# TAStm32_v4.net
KiCad netlist of a schematic drawn in EAGLE
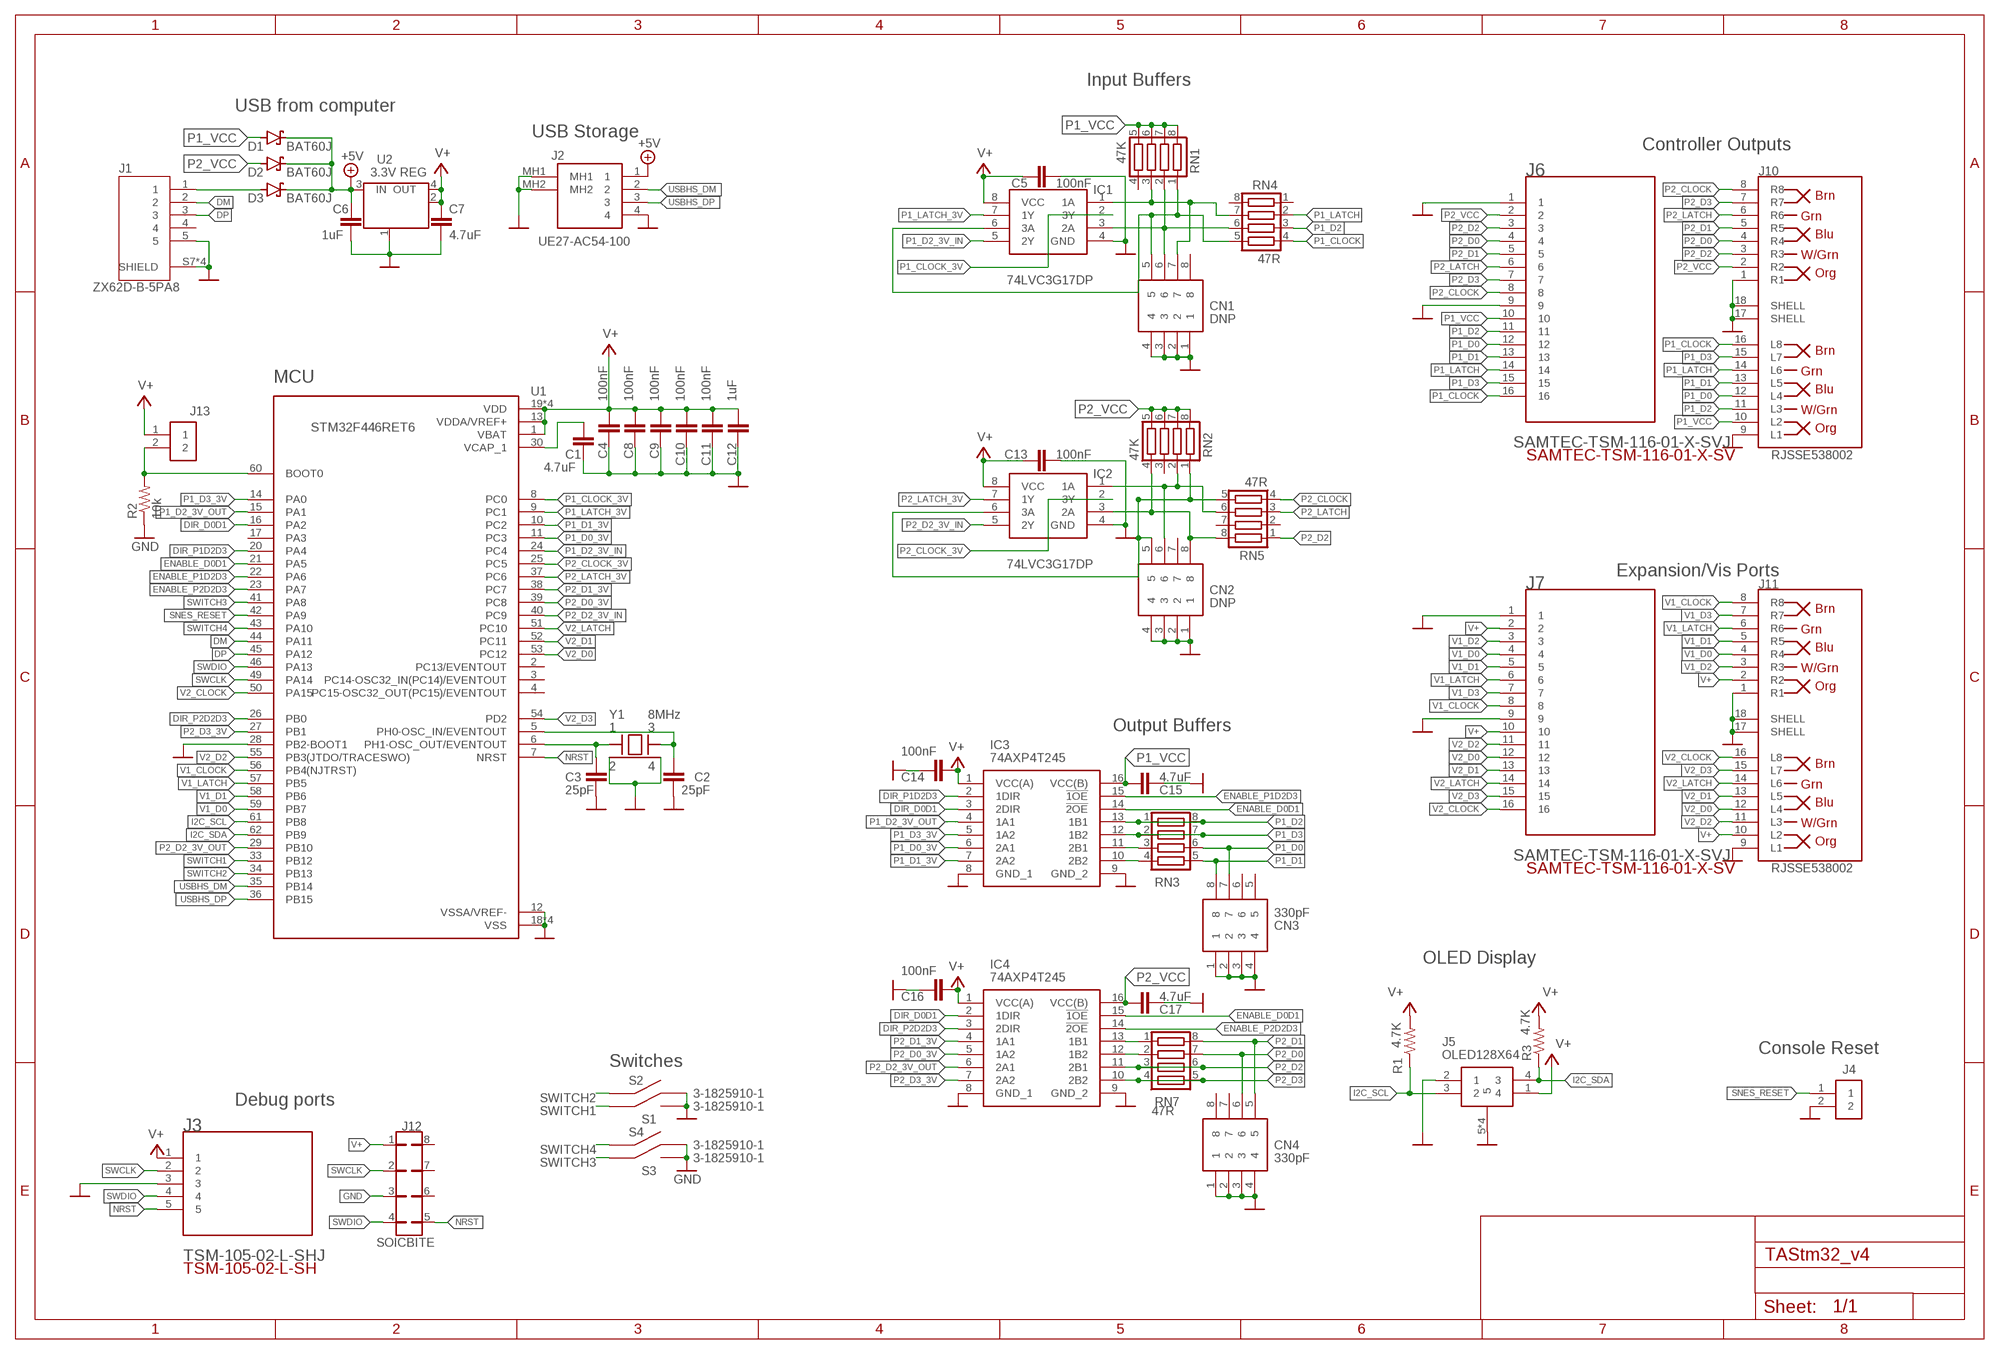
[diagram p0: schematic, sheet 1]

(export (version "E")
  (design (tool "Eeschema 10.0.6"))
  (components
    (comp (ref "C1")
      (value "4.7uF")
      (footprint "eagle-import:C0603K")
      (libsource (lib "eagle-import") (part "C-EUC0603K"))
    )
    (comp (ref "C2")
      (value "25pF")
      (footprint "eagle-import:C0603K")
      (libsource (lib "eagle-import") (part "C-EUC0603K"))
    )
    (comp (ref "C3")
      (value "25pF")
      (footprint "eagle-import:C0603K")
      (libsource (lib "eagle-import") (part "C-EUC0603K"))
    )
    (comp (ref "C4")
      (value "100nF")
      (footprint "eagle-import:C0603K")
      (libsource (lib "eagle-import") (part "C-EUC0603K"))
    )
    (comp (ref "C5")
      (value "100nF")
      (footprint "eagle-import:C0603K")
      (libsource (lib "eagle-import") (part "C-EUC0603K"))
    )
    (comp (ref "C6")
      (value "1uF")
      (footprint "eagle-import:C0603K")
      (libsource (lib "eagle-import") (part "C-EUC0603K"))
    )
    (comp (ref "C7")
      (value "4.7uF")
      (footprint "eagle-import:C0603K")
      (libsource (lib "eagle-import") (part "C-EUC0603K"))
    )
    (comp (ref "C8")
      (value "100nF")
      (footprint "eagle-import:C0603K")
      (libsource (lib "eagle-import") (part "C-EUC0603K"))
    )
    (comp (ref "C9")
      (value "100nF")
      (footprint "eagle-import:C0603K")
      (libsource (lib "eagle-import") (part "C-EUC0603K"))
    )
    (comp (ref "C10")
      (value "100nF")
      (footprint "eagle-import:C0603K")
      (libsource (lib "eagle-import") (part "C-EUC0603K"))
    )
    (comp (ref "C11")
      (value "100nF")
      (footprint "eagle-import:C0603K")
      (libsource (lib "eagle-import") (part "C-EUC0603K"))
    )
    (comp (ref "C12")
      (value "1uF")
      (footprint "eagle-import:C0603K")
      (libsource (lib "eagle-import") (part "C-EUC0603K"))
    )
    (comp (ref "C13")
      (value "100nF")
      (footprint "eagle-import:C0603K")
      (libsource (lib "eagle-import") (part "C-EUC0603K"))
    )
    (comp (ref "C14")
      (value "100nF")
      (footprint "eagle-import:C0603K")
      (libsource (lib "eagle-import") (part "C-EUC0603K"))
    )
    (comp (ref "C15")
      (value "4.7uF")
      (footprint "eagle-import:C0603K")
      (libsource (lib "eagle-import") (part "C-EUC0603K"))
    )
    (comp (ref "C16")
      (value "100nF")
      (footprint "eagle-import:C0603K")
      (libsource (lib "eagle-import") (part "C-EUC0603K"))
    )
    (comp (ref "C17")
      (value "4.7uF")
      (footprint "eagle-import:C0603K")
      (libsource (lib "eagle-import") (part "C-EUC0603K"))
    )
    (comp (ref "CN1")
      (value "DNP")
      (footprint "eagle-import:CA0612KRX7R7BB104")
      (fields
        (field (name "MANUFACTURER_PART_NUMBER") "CA0612KRX7R7BB104")
        (field (name "MOUSER_PART_NUMBER") "603-CA612KRX7R7BB104")
      )
      (libsource (lib "eagle-import") (part "CA0612KRX7R7BB104"))
    )
    (comp (ref "CN2")
      (value "DNP")
      (footprint "eagle-import:CA0612KRX7R7BB104")
      (fields
        (field (name "MANUFACTURER_PART_NUMBER") "CA0612KRX7R7BB104")
        (field (name "MOUSER_PART_NUMBER") "603-CA612KRX7R7BB104")
      )
      (libsource (lib "eagle-import") (part "CA0612KRX7R7BB104"))
    )
    (comp (ref "CN3")
      (value "330pF")
      (footprint "eagle-import:CA0612KRX7R7BB104")
      (fields
        (field (name "MANUFACTURER_PART_NUMBER") "CA0612KRX7R7BB104")
        (field (name "MOUSER_PART_NUMBER") "603-CA612KRX7R7BB104")
      )
      (libsource (lib "eagle-import") (part "CA0612KRX7R7BB104"))
    )
    (comp (ref "CN4")
      (value "330pF")
      (footprint "eagle-import:CA0612KRX7R7BB104")
      (fields
        (field (name "MANUFACTURER_PART_NUMBER") "CA0612KRX7R7BB104")
        (field (name "MOUSER_PART_NUMBER") "603-CA612KRX7R7BB104")
      )
      (libsource (lib "eagle-import") (part "CA0612KRX7R7BB104"))
    )
    (comp (ref "D1")
      (value "BAT60J")
      (footprint "eagle-import:DIODE_SOD323_ST")
      (libsource (lib "eagle-import") (part "DIODE_BAT60J"))
    )
    (comp (ref "D2")
      (value "BAT60J")
      (footprint "eagle-import:DIODE_SOD323_ST")
      (libsource (lib "eagle-import") (part "DIODE_BAT60J"))
    )
    (comp (ref "D3")
      (value "BAT60J")
      (footprint "eagle-import:DIODE_SOD323_ST")
      (libsource (lib "eagle-import") (part "DIODE_BAT60J"))
    )
    (comp (ref "IC1")
      (value "74LVC3G17DP")
      (footprint "eagle-import:SOP65P400X110-8N")
      (fields
        (field (name "MANUFACTURER_PART_NUMBER") "74HCT3G07DP-Q100H")
        (field (name "RS_PART_NUMBER") "1532947P")
      )
      (libsource (lib "eagle-import") (part "74HCT3G07DP-Q100H"))
    )
    (comp (ref "IC2")
      (value "74LVC3G17DP")
      (footprint "eagle-import:SOP65P400X110-8N")
      (fields
        (field (name "MANUFACTURER_PART_NUMBER") "74HCT3G07DP-Q100H")
        (field (name "RS_PART_NUMBER") "1532947P")
      )
      (libsource (lib "eagle-import") (part "74HCT3G07DP-Q100H"))
    )
    (comp (ref "IC3")
      (value "74AXP4T245")
      (footprint "eagle-import:SOP65P640X110-16N")
      (fields
        (field (name "MANUFACTURER_PART_NUMBER") "74AVCH4T245PW,118")
        (field (name "MOUSER_PART_NUMBER") "771-74AVCH4T245PW118")
      )
      (libsource (lib "eagle-import") (part "74AVCH4T245PW,118"))
    )
    (comp (ref "IC4")
      (value "74AXP4T245")
      (footprint "eagle-import:SOP65P640X110-16N")
      (fields
        (field (name "MANUFACTURER_PART_NUMBER") "74AVCH4T245PW,118")
        (field (name "MOUSER_PART_NUMBER") "771-74AVCH4T245PW118")
      )
      (libsource (lib "eagle-import") (part "74AVCH4T245PW,118"))
    )
    (comp (ref "J1")
      (value "ZX62D-B-5PA8")
      (footprint "eagle-import:HIROSE_ZX62D-B-5PA8")
      (fields (field (name "MF") "Hirose"))
      (libsource (lib "eagle-import") (part "ZX62D-B-5PA8"))
    )
    (comp (ref "J2")
      (value "UE27-AC54-100")
      (footprint "eagle-import:UE27AC54100")
      (fields (field (name "MOUSER_PART_NUMBER") "523-UE27-AC54-100"))
      (libsource (lib "eagle-import") (part "UE27-AC54-100"))
    )
    (comp (ref "J3")
      (value "TSM-105-02-L-SHJ")
      (footprint "eagle-import:TSM-105-02-L-SH")
      (fields (field (name "MF") "Samtec") (field (name "MP") "TSM-105-02-L-SH"))
      (libsource (lib "eagle-import") (part "TSM-105-02-L-SHJ"))
    )
    (comp (ref "J4")
      (value "CONSOLE_RESET")
      (footprint "eagle-import:SAMTEC-TSM-102-01-X-SH")
      (libsource (lib "eagle-import") (part "SAMTEC-TSM-102-01-X-SH_SAMTEC-TSM-102-01-X-SH"))
    )
    (comp (ref "J5")
      (value "OLED128X64")
      (footprint "eagle-import:OLED")
      (libsource (lib "eagle-import") (part "OLED128X64"))
    )
    (comp (ref "J6")
      (value "SAMTEC-TSM-116-01-X-SVJ")
      (footprint "eagle-import:SAMTEC-TSM-116-01-X-SV")
      (libsource (lib "eagle-import") (part "SAMTEC-TSM-116-01-X-SVJ"))
    )
    (comp (ref "J7")
      (value "SAMTEC-TSM-116-01-X-SVJ")
      (footprint "eagle-import:SAMTEC-TSM-116-01-X-SV")
      (libsource (lib "eagle-import") (part "SAMTEC-TSM-116-01-X-SVJ"))
    )
    (comp (ref "J10")
      (value "RJSSE538002")
      (footprint "eagle-import:AMPHENOL_RJSSE538002")
      (libsource (lib "eagle-import") (part "RJSSE538002_RJSSE538002"))
    )
    (comp (ref "J11")
      (value "RJSSE538002")
      (footprint "eagle-import:AMPHENOL_RJSSE538002")
      (libsource (lib "eagle-import") (part "RJSSE538002_RJSSE538002"))
    )
    (comp (ref "J12")
      (value "SOICBITE")
      (footprint "eagle-import:SOICBITE")
      (libsource (lib "eagle-import") (part "SOICBITE"))
    )
    (comp (ref "J13")
      (value "CONSOLE_RESET")
      (footprint "eagle-import:SAMTEC-TSM-102-01-X-SH")
      (libsource (lib "eagle-import") (part "SAMTEC-TSM-102-01-X-SH_SAMTEC-TSM-102-01-X-SH"))
    )
    (comp (ref "R1")
      (value "4.7K")
      (footprint "eagle-import:R0805")
      (libsource (lib "eagle-import") (part "R-US_R0805"))
    )
    (comp (ref "R2")
      (value "10k")
      (footprint "eagle-import:R0805")
      (libsource (lib "eagle-import") (part "R-US_R0805"))
    )
    (comp (ref "R3")
      (value "4.7K")
      (footprint "eagle-import:R0805")
      (libsource (lib "eagle-import") (part "R-US_R0805"))
    )
    (comp (ref "RN1")
      (value "47K")
      (footprint "eagle-import:CTS742C083")
      (libsource (lib "eagle-import") (part "CTS742C083"))
    )
    (comp (ref "RN2")
      (value "47K")
      (footprint "eagle-import:CTS742C083")
      (libsource (lib "eagle-import") (part "CTS742C083"))
    )
    (comp (ref "RN3")
      (value "CTS742C083")
      (footprint "eagle-import:CTS742C083")
      (libsource (lib "eagle-import") (part "CTS742C083"))
    )
    (comp (ref "RN4")
      (value "47R")
      (footprint "eagle-import:CTS742C083")
      (libsource (lib "eagle-import") (part "CTS742C083"))
    )
    (comp (ref "RN5")
      (value "47R")
      (footprint "eagle-import:CTS742C083")
      (libsource (lib "eagle-import") (part "CTS742C083"))
    )
    (comp (ref "RN7")
      (value "47R")
      (footprint "eagle-import:CTS742C083")
      (libsource (lib "eagle-import") (part "CTS742C083"))
    )
    (comp (ref "S1")
      (value "3-1825910-1")
      (footprint "eagle-import:3-1825910-1_318259101")
      (libsource (lib "eagle-import") (part "3-1825910-1_SWITCHN"))
    )
    (comp (ref "S2")
      (value "3-1825910-1")
      (footprint "eagle-import:3-1825910-1_318259101")
      (libsource (lib "eagle-import") (part "3-1825910-1_SWITCHN"))
    )
    (comp (ref "S3")
      (value "3-1825910-1")
      (footprint "eagle-import:3-1825910-1_318259101")
      (libsource (lib "eagle-import") (part "3-1825910-1_SWITCHN"))
    )
    (comp (ref "S4")
      (value "3-1825910-1")
      (footprint "eagle-import:3-1825910-1_318259101")
      (libsource (lib "eagle-import") (part "3-1825910-1_SWITCHN"))
    )
    (comp (ref "U1")
      (value "STM32F446RET6")
      (footprint "eagle-import:QFP50P1200X1200X160-64N")
      (libsource (lib "eagle-import") (part "STM32F446RET7"))
    )
    (comp (ref "U2")
      (value "3.3V REG")
      (footprint "eagle-import:SOT223")
      (libsource (lib "eagle-import") (part "MC33269ST-3.3T3"))
    )
    (comp (ref "Y1")
      (value "8MHz")
      (footprint "eagle-import:DFN-4")
      (libsource (lib "eagle-import") (part "ABMM-8.000MHZ-B2-T_ABMM-8.000MHZ-B2-T"))
    )
  )
  (nets
    (net (code "1") (name "+5V") (class "Default")
      (node (ref "C6") (pin "2") (pinfunction "2_2") (pintype "passive"))
      (node (ref "D1") (pin "C") (pinfunction "C_C") (pintype "passive"))
      (node (ref "D2") (pin "C") (pinfunction "C_C") (pintype "passive"))
      (node (ref "D3") (pin "C") (pinfunction "C_C") (pintype "passive"))
      (node (ref "J2") (pin "1") (pinfunction "1_1") (pintype "bidirectional"))
      (node (ref "U2") (pin "3") (pinfunction "IN_3") (pintype "input"))
    )
    (net (code "2") (name "DIR_D0D1") (class "Default")
      (node (ref "IC3") (pin "3") (pinfunction "2DIR_3") (pintype "bidirectional"))
      (node (ref "IC4") (pin "2") (pinfunction "1DIR_2") (pintype "bidirectional"))
      (node (ref "U1") (pin "16") (pinfunction "PA2_16") (pintype "bidirectional"))
    )
    (net (code "3") (name "DIR_P1D2D3") (class "Default")
      (node (ref "IC3") (pin "2") (pinfunction "1DIR_2") (pintype "bidirectional"))
      (node (ref "U1") (pin "20") (pinfunction "PA4_20") (pintype "bidirectional"))
    )
    (net (code "4") (name "DIR_P2D2D3") (class "Default")
      (node (ref "IC4") (pin "3") (pinfunction "2DIR_3") (pintype "bidirectional"))
      (node (ref "U1") (pin "26") (pinfunction "PB0_26") (pintype "bidirectional"))
    )
    (net (code "5") (name "DM") (class "Default")
      (node (ref "J1") (pin "2") (pinfunction "2_2") (pintype "passive"))
      (node (ref "U1") (pin "44") (pinfunction "PA11_44") (pintype "bidirectional"))
    )
    (net (code "6") (name "DP") (class "Default")
      (node (ref "J1") (pin "3") (pinfunction "3_3") (pintype "passive"))
      (node (ref "U1") (pin "45") (pinfunction "PA12_45") (pintype "bidirectional"))
    )
    (net (code "7") (name "ENABLE_D0D1") (class "Default")
      (node (ref "IC3") (pin "14") (pinfunction "~{2OE}_14") (pintype "bidirectional"))
      (node (ref "IC4") (pin "15") (pinfunction "~{1OE}_15") (pintype "bidirectional"))
      (node (ref "U1") (pin "21") (pinfunction "PA5_21") (pintype "bidirectional"))
    )
    (net (code "8") (name "ENABLE_P1D2D3") (class "Default")
      (node (ref "IC3") (pin "15") (pinfunction "~{1OE}_15") (pintype "bidirectional"))
      (node (ref "U1") (pin "22") (pinfunction "PA6_22") (pintype "bidirectional"))
    )
    (net (code "9") (name "ENABLE_P2D2D3") (class "Default")
      (node (ref "IC4") (pin "14") (pinfunction "~{2OE}_14") (pintype "bidirectional"))
      (node (ref "U1") (pin "23") (pinfunction "PA7_23") (pintype "bidirectional"))
    )
    (net (code "10") (name "GND") (class "Default")
      (node (ref "C1") (pin "2") (pinfunction "2_2") (pintype "passive"))
      (node (ref "C10") (pin "1") (pinfunction "1_1") (pintype "passive"))
      (node (ref "C11") (pin "1") (pinfunction "1_1") (pintype "passive"))
      (node (ref "C12") (pin "1") (pinfunction "1_1") (pintype "passive"))
      (node (ref "C13") (pin "2") (pinfunction "2_2") (pintype "passive"))
      (node (ref "C14") (pin "1") (pinfunction "1_1") (pintype "passive"))
      (node (ref "C15") (pin "2") (pinfunction "2_2") (pintype "passive"))
      (node (ref "C16") (pin "1") (pinfunction "1_1") (pintype "passive"))
      (node (ref "C17") (pin "2") (pinfunction "2_2") (pintype "passive"))
      (node (ref "C2") (pin "1") (pinfunction "1_1") (pintype "passive"))
      (node (ref "C3") (pin "1") (pinfunction "1_1") (pintype "passive"))
      (node (ref "C4") (pin "1") (pinfunction "1_1") (pintype "passive"))
      (node (ref "C5") (pin "2") (pinfunction "2_2") (pintype "passive"))
      (node (ref "C6") (pin "1") (pinfunction "1_1") (pintype "passive"))
      (node (ref "C7") (pin "1") (pinfunction "1_1") (pintype "passive"))
      (node (ref "C8") (pin "1") (pinfunction "1_1") (pintype "passive"))
      (node (ref "C9") (pin "1") (pinfunction "1_1") (pintype "passive"))
      (node (ref "CN1") (pin "1") (pinfunction "1_1") (pintype "bidirectional"))
      (node (ref "CN1") (pin "2") (pinfunction "2_2") (pintype "bidirectional"))
      (node (ref "CN1") (pin "3") (pinfunction "3_3") (pintype "bidirectional"))
      (node (ref "CN1") (pin "4") (pinfunction "4_4") (pintype "bidirectional"))
      (node (ref "CN2") (pin "1") (pinfunction "1_1") (pintype "bidirectional"))
      (node (ref "CN2") (pin "2") (pinfunction "2_2") (pintype "bidirectional"))
      (node (ref "CN2") (pin "3") (pinfunction "3_3") (pintype "bidirectional"))
      (node (ref "CN2") (pin "4") (pinfunction "4_4") (pintype "bidirectional"))
      (node (ref "CN3") (pin "1") (pinfunction "1_1") (pintype "bidirectional"))
      (node (ref "CN3") (pin "2") (pinfunction "2_2") (pintype "bidirectional"))
      (node (ref "CN3") (pin "3") (pinfunction "3_3") (pintype "bidirectional"))
      (node (ref "CN3") (pin "4") (pinfunction "4_4") (pintype "bidirectional"))
      (node (ref "CN4") (pin "1") (pinfunction "1_1") (pintype "bidirectional"))
      (node (ref "CN4") (pin "2") (pinfunction "2_2") (pintype "bidirectional"))
      (node (ref "CN4") (pin "3") (pinfunction "3_3") (pintype "bidirectional"))
      (node (ref "CN4") (pin "4") (pinfunction "4_4") (pintype "bidirectional"))
      (node (ref "IC1") (pin "4") (pinfunction "GND_4") (pintype "bidirectional"))
      (node (ref "IC2") (pin "4") (pinfunction "GND_4") (pintype "bidirectional"))
      (node (ref "IC3") (pin "8") (pinfunction "GND_1_8") (pintype "bidirectional"))
      (node (ref "IC3") (pin "9") (pinfunction "GND_2_9") (pintype "bidirectional"))
      (node (ref "IC4") (pin "8") (pinfunction "GND_1_8") (pintype "bidirectional"))
      (node (ref "IC4") (pin "9") (pinfunction "GND_2_9") (pintype "bidirectional"))
      (node (ref "J1") (pin "5") (pinfunction "5_5") (pintype "passive"))
      (node (ref "J1") (pin "S10") (pinfunction "SHIELD_S10") (pintype "power_in"))
      (node (ref "J1") (pin "S7") (pinfunction "SHIELD_S7") (pintype "power_in"))
      (node (ref "J1") (pin "S8") (pinfunction "SHIELD_S8") (pintype "power_in"))
      (node (ref "J1") (pin "S9") (pinfunction "SHIELD_S9") (pintype "power_in"))
      (node (ref "J10") (pin "1") (pinfunction "R1_1") (pintype "bidirectional"))
      (node (ref "J10") (pin "17") (pinfunction "SHELL_17") (pintype "passive"))
      (node (ref "J10") (pin "18") (pinfunction "SHELL_18") (pintype "passive"))
      (node (ref "J10") (pin "9") (pinfunction "L1_9") (pintype "bidirectional"))
      (node (ref "J11") (pin "1") (pinfunction "R1_1") (pintype "bidirectional"))
      (node (ref "J11") (pin "17") (pinfunction "SHELL_17") (pintype "passive"))
      (node (ref "J11") (pin "18") (pinfunction "SHELL_18") (pintype "passive"))
      (node (ref "J11") (pin "9") (pinfunction "L1_9") (pintype "bidirectional"))
      (node (ref "J12") (pin "3") (pinfunction "P$3_3") (pintype "passive"))
      (node (ref "J2") (pin "4") (pinfunction "4_4") (pintype "bidirectional"))
      (node (ref "J2") (pin "MH1") (pinfunction "MH1_MH1") (pintype "bidirectional"))
      (node (ref "J2") (pin "MH2") (pinfunction "MH2_MH2") (pintype "bidirectional"))
      (node (ref "J3") (pin "3") (pinfunction "3_3") (pintype "bidirectional"))
      (node (ref "J4") (pin "2") (pinfunction "2_2") (pintype "bidirectional"))
      (node (ref "J5") (pin "2") (pinfunction "1_2") (pintype "bidirectional"))
      (node (ref "J5") (pin "5") (pinfunction "5_5") (pintype "bidirectional"))
      (node (ref "J5") (pin "6") (pinfunction "5_6") (pintype "bidirectional"))
      (node (ref "J5") (pin "7") (pinfunction "5_7") (pintype "bidirectional"))
      (node (ref "J5") (pin "8") (pinfunction "5_8") (pintype "bidirectional"))
      (node (ref "J6") (pin "1") (pinfunction "1_1") (pintype "bidirectional"))
      (node (ref "J6") (pin "9") (pinfunction "9_9") (pintype "bidirectional"))
      (node (ref "J7") (pin "1") (pinfunction "1_1") (pintype "bidirectional"))
      (node (ref "J7") (pin "9") (pinfunction "9_9") (pintype "bidirectional"))
      (node (ref "R2") (pin "1") (pinfunction "1_1") (pintype "passive"))
      (node (ref "S1") (pin "3") (pinfunction "P$2_3") (pintype "bidirectional"))
      (node (ref "S1") (pin "4") (pinfunction "P$2_4") (pintype "bidirectional"))
      (node (ref "S2") (pin "3") (pinfunction "P$2_3") (pintype "bidirectional"))
      (node (ref "S2") (pin "4") (pinfunction "P$2_4") (pintype "bidirectional"))
      (node (ref "S3") (pin "3") (pinfunction "P$2_3") (pintype "bidirectional"))
      (node (ref "S3") (pin "4") (pinfunction "P$2_4") (pintype "bidirectional"))
      (node (ref "S4") (pin "3") (pinfunction "P$2_3") (pintype "bidirectional"))
      (node (ref "S4") (pin "4") (pinfunction "P$2_4") (pintype "bidirectional"))
      (node (ref "U1") (pin "12") (pinfunction "VSSA/VREF-_12") (pintype "power_in"))
      (node (ref "U1") (pin "18") (pinfunction "VSS_18") (pintype "power_in"))
      (node (ref "U1") (pin "28") (pinfunction "PB2-BOOT1_28") (pintype "bidirectional"))
      (node (ref "U1") (pin "31") (pinfunction "VSS_31") (pintype "power_in"))
      (node (ref "U1") (pin "47") (pinfunction "VSS_47") (pintype "power_in"))
      (node (ref "U1") (pin "63") (pinfunction "VSS_63") (pintype "power_in"))
      (node (ref "U2") (pin "1") (pinfunction "GND/ADJ_1") (pintype "input"))
      (node (ref "Y1") (pin "2") (pinfunction "2_2") (pintype "bidirectional"))
      (node (ref "Y1") (pin "4") (pinfunction "4_4") (pintype "bidirectional"))
    )
    (net (code "11") (name "I2C_SCL") (class "Default")
      (node (ref "J5") (pin "3") (pinfunction "2_3") (pintype "bidirectional"))
      (node (ref "R1") (pin "1") (pinfunction "1_1") (pintype "passive"))
      (node (ref "U1") (pin "61") (pinfunction "PB8_61") (pintype "bidirectional"))
    )
    (net (code "12") (name "I2C_SDA") (class "Default")
      (node (ref "J5") (pin "4") (pinfunction "3_4") (pintype "bidirectional"))
      (node (ref "R3") (pin "1") (pinfunction "1_1") (pintype "passive"))
      (node (ref "U1") (pin "62") (pinfunction "PB9_62") (pintype "bidirectional"))
    )
    (net (code "13") (name "NRST") (class "Default")
      (node (ref "J12") (pin "5") (pinfunction "P$5_5") (pintype "passive"))
      (node (ref "J3") (pin "5") (pinfunction "5_5") (pintype "bidirectional"))
      (node (ref "U1") (pin "7") (pinfunction "NRST_7") (pintype "bidirectional"))
    )
    (net (code "14") (name "Net-(D3-PadA)") (class "Default")
      (node (ref "D3") (pin "A") (pinfunction "A_A") (pintype "passive"))
      (node (ref "J1") (pin "1") (pinfunction "1_1") (pintype "passive"))
    )
    (net (code "15") (name "Net-(IC1-1A)") (class "Default")
      (node (ref "CN1") (pin "7") (pinfunction "7_7") (pintype "bidirectional"))
      (node (ref "IC1") (pin "1") (pinfunction "1A_1") (pintype "bidirectional"))
      (node (ref "RN1") (pin "3") (pinfunction "3_3") (pintype "passive"))
      (node (ref "RN4") (pin "7") (pinfunction "7_7") (pintype "passive"))
    )
    (net (code "16") (name "Net-(IC1-2A)") (class "Default")
      (node (ref "CN1") (pin "6") (pinfunction "6_6") (pintype "bidirectional"))
      (node (ref "IC1") (pin "3") (pinfunction "2A_3") (pintype "bidirectional"))
      (node (ref "RN1") (pin "2") (pinfunction "2_2") (pintype "passive"))
      (node (ref "RN4") (pin "6") (pinfunction "6_6") (pintype "passive"))
    )
    (net (code "17") (name "Net-(IC1-3A)") (class "Default")
      (node (ref "CN1") (pin "5") (pinfunction "5_5") (pintype "bidirectional"))
      (node (ref "IC1") (pin "6") (pinfunction "3A_6") (pintype "bidirectional"))
      (node (ref "RN1") (pin "1") (pinfunction "1_1") (pintype "passive"))
      (node (ref "RN4") (pin "5") (pinfunction "5_5") (pintype "passive"))
    )
    (net (code "18") (name "Net-(IC2-1A)") (class "Default")
      (node (ref "CN2") (pin "6") (pinfunction "6_6") (pintype "bidirectional"))
      (node (ref "IC2") (pin "1") (pinfunction "1A_1") (pintype "bidirectional"))
      (node (ref "RN2") (pin "2") (pinfunction "2_2") (pintype "passive"))
      (node (ref "RN5") (pin "6") (pinfunction "6_6") (pintype "passive"))
    )
    (net (code "19") (name "Net-(IC2-2A)") (class "Default")
      (node (ref "CN2") (pin "8") (pinfunction "8_8") (pintype "bidirectional"))
      (node (ref "IC2") (pin "3") (pinfunction "2A_3") (pintype "bidirectional"))
      (node (ref "RN2") (pin "4") (pinfunction "4_4") (pintype "passive"))
      (node (ref "RN5") (pin "8") (pinfunction "8_8") (pintype "passive"))
    )
    (net (code "20") (name "Net-(IC2-3A)") (class "Default")
      (node (ref "CN2") (pin "5") (pinfunction "5_5") (pintype "bidirectional"))
      (node (ref "IC2") (pin "6") (pinfunction "3A_6") (pintype "bidirectional"))
      (node (ref "RN2") (pin "1") (pinfunction "1_1") (pintype "passive"))
      (node (ref "RN5") (pin "5") (pinfunction "5_5") (pintype "passive"))
    )
    (net (code "21") (name "Net-(IC3-2B1)") (class "Default")
      (node (ref "IC3") (pin "11") (pinfunction "2B1_11") (pintype "bidirectional"))
      (node (ref "RN3") (pin "3") (pinfunction "3_3") (pintype "passive"))
    )
    (net (code "22") (name "Net-(IC3-2B2)") (class "Default")
      (node (ref "IC3") (pin "10") (pinfunction "2B2_10") (pintype "bidirectional"))
      (node (ref "RN3") (pin "4") (pinfunction "4_4") (pintype "passive"))
    )
    (net (code "23") (name "Net-(IC4-1B1)") (class "Default")
      (node (ref "IC4") (pin "13") (pinfunction "1B1_13") (pintype "bidirectional"))
      (node (ref "RN7") (pin "1") (pinfunction "1_1") (pintype "passive"))
    )
    (net (code "24") (name "Net-(IC4-1B2)") (class "Default")
      (node (ref "IC4") (pin "12") (pinfunction "1B2_12") (pintype "bidirectional"))
      (node (ref "RN7") (pin "2") (pinfunction "2_2") (pintype "passive"))
    )
    (net (code "25") (name "Net-(U1-BOOT0)") (class "Default")
      (node (ref "J13") (pin "2") (pinfunction "2_2") (pintype "bidirectional"))
      (node (ref "R2") (pin "2") (pinfunction "2_2") (pintype "passive"))
      (node (ref "U1") (pin "60") (pinfunction "BOOT0_60") (pintype "input"))
    )
    (net (code "26") (name "Net-(U1-PH0-OSC_IN{slash}EVENTOUT)") (class "Default")
      (node (ref "C2") (pin "2") (pinfunction "2_2") (pintype "passive"))
      (node (ref "U1") (pin "5") (pinfunction "PH0-OSC_IN/EVENTOUT_5") (pintype "bidirectional"))
      (node (ref "Y1") (pin "3") (pinfunction "3_3") (pintype "bidirectional"))
    )
    (net (code "27") (name "Net-(U1-PH1-OSC_OUT{slash}EVENTOUT)") (class "Default")
      (node (ref "C3") (pin "2") (pinfunction "2_2") (pintype "passive"))
      (node (ref "U1") (pin "6") (pinfunction "PH1-OSC_OUT/EVENTOUT_6") (pintype "bidirectional"))
      (node (ref "Y1") (pin "1") (pinfunction "1_1") (pintype "bidirectional"))
    )
    (net (code "28") (name "Net-(U1-VCAP_1)") (class "Default")
      (node (ref "C1") (pin "1") (pinfunction "1_1") (pintype "passive"))
      (node (ref "U1") (pin "30") (pinfunction "VCAP_1_30") (pintype "power_in"))
    )
    (net (code "29") (name "P1_CLOCK") (class "Default")
      (node (ref "J10") (pin "16") (pinfunction "L8_16") (pintype "bidirectional"))
      (node (ref "J6") (pin "16") (pinfunction "16_16") (pintype "bidirectional"))
      (node (ref "RN4") (pin "4") (pinfunction "4_4") (pintype "passive"))
    )
    (net (code "30") (name "P1_CLOCK_3V") (class "Default")
      (node (ref "IC1") (pin "2") (pinfunction "3Y_2") (pintype "bidirectional"))
      (node (ref "U1") (pin "8") (pinfunction "PC0_8") (pintype "bidirectional"))
    )
    (net (code "31") (name "P1_D0") (class "Default")
      (node (ref "CN3") (pin "7") (pinfunction "7_7") (pintype "bidirectional"))
      (node (ref "J10") (pin "12") (pinfunction "L4_12") (pintype "bidirectional"))
      (node (ref "J6") (pin "12") (pinfunction "12_12") (pintype "bidirectional"))
      (node (ref "RN3") (pin "6") (pinfunction "6_6") (pintype "passive"))
    )
    (net (code "32") (name "P1_D0_3V") (class "Default")
      (node (ref "IC3") (pin "6") (pinfunction "2A1_6") (pintype "bidirectional"))
      (node (ref "U1") (pin "11") (pinfunction "PC3_11") (pintype "bidirectional"))
    )
    (net (code "33") (name "P1_D1") (class "Default")
      (node (ref "CN3") (pin "8") (pinfunction "8_8") (pintype "bidirectional"))
      (node (ref "J10") (pin "13") (pinfunction "L5_13") (pintype "bidirectional"))
      (node (ref "J6") (pin "13") (pinfunction "13_13") (pintype "bidirectional"))
      (node (ref "RN3") (pin "5") (pinfunction "5_5") (pintype "passive"))
    )
    (net (code "34") (name "P1_D1_3V") (class "Default")
      (node (ref "IC3") (pin "7") (pinfunction "2A2_7") (pintype "bidirectional"))
      (node (ref "U1") (pin "10") (pinfunction "PC2_10") (pintype "bidirectional"))
    )
    (net (code "35") (name "P1_D2") (class "Default")
      (node (ref "IC3") (pin "13") (pinfunction "1B1_13") (pintype "bidirectional"))
      (node (ref "J10") (pin "11") (pinfunction "L3_11") (pintype "bidirectional"))
      (node (ref "J6") (pin "11") (pinfunction "11_11") (pintype "bidirectional"))
      (node (ref "RN3") (pin "1") (pinfunction "1_1") (pintype "passive"))
      (node (ref "RN3") (pin "8") (pinfunction "8_8") (pintype "passive"))
      (node (ref "RN4") (pin "3") (pinfunction "3_3") (pintype "passive"))
    )
    (net (code "36") (name "P1_D2_3V_IN") (class "Default")
      (node (ref "IC1") (pin "5") (pinfunction "2Y_5") (pintype "bidirectional"))
      (node (ref "U1") (pin "24") (pinfunction "PC4_24") (pintype "bidirectional"))
    )
    (net (code "37") (name "P1_D2_3V_OUT") (class "Default")
      (node (ref "IC3") (pin "4") (pinfunction "1A1_4") (pintype "bidirectional"))
      (node (ref "U1") (pin "15") (pinfunction "PA1_15") (pintype "bidirectional"))
    )
    (net (code "38") (name "P1_D3") (class "Default")
      (node (ref "IC3") (pin "12") (pinfunction "1B2_12") (pintype "bidirectional"))
      (node (ref "J10") (pin "15") (pinfunction "L7_15") (pintype "bidirectional"))
      (node (ref "J6") (pin "15") (pinfunction "15_15") (pintype "bidirectional"))
      (node (ref "RN3") (pin "2") (pinfunction "2_2") (pintype "passive"))
      (node (ref "RN3") (pin "7") (pinfunction "7_7") (pintype "passive"))
    )
    (net (code "39") (name "P1_D3_3V") (class "Default")
      (node (ref "IC3") (pin "5") (pinfunction "1A2_5") (pintype "bidirectional"))
      (node (ref "U1") (pin "14") (pinfunction "PA0_14") (pintype "bidirectional"))
    )
    (net (code "40") (name "P1_LATCH") (class "Default")
      (node (ref "J10") (pin "14") (pinfunction "L6_14") (pintype "bidirectional"))
      (node (ref "J6") (pin "14") (pinfunction "14_14") (pintype "bidirectional"))
      (node (ref "RN4") (pin "2") (pinfunction "2_2") (pintype "passive"))
    )
    (net (code "41") (name "P1_LATCH_3V") (class "Default")
      (node (ref "IC1") (pin "7") (pinfunction "1Y_7") (pintype "bidirectional"))
      (node (ref "U1") (pin "9") (pinfunction "PC1_9") (pintype "bidirectional"))
    )
    (net (code "42") (name "P1_VCC") (class "Default")
      (node (ref "C15") (pin "1") (pinfunction "1_1") (pintype "passive"))
      (node (ref "D1") (pin "A") (pinfunction "A_A") (pintype "passive"))
      (node (ref "IC3") (pin "16") (pinfunction "VCC(B)_16") (pintype "bidirectional"))
      (node (ref "J10") (pin "10") (pinfunction "L2_10") (pintype "bidirectional"))
      (node (ref "J6") (pin "10") (pinfunction "10_10") (pintype "bidirectional"))
      (node (ref "RN1") (pin "5") (pinfunction "5_5") (pintype "passive"))
      (node (ref "RN1") (pin "6") (pinfunction "6_6") (pintype "passive"))
      (node (ref "RN1") (pin "7") (pinfunction "7_7") (pintype "passive"))
      (node (ref "RN1") (pin "8") (pinfunction "8_8") (pintype "passive"))
    )
    (net (code "43") (name "P2_CLOCK") (class "Default")
      (node (ref "J10") (pin "8") (pinfunction "R8_8") (pintype "bidirectional"))
      (node (ref "J6") (pin "8") (pinfunction "8_8") (pintype "bidirectional"))
      (node (ref "RN5") (pin "4") (pinfunction "4_4") (pintype "passive"))
    )
    (net (code "44") (name "P2_CLOCK_3V") (class "Default")
      (node (ref "IC2") (pin "2") (pinfunction "3Y_2") (pintype "bidirectional"))
      (node (ref "U1") (pin "25") (pinfunction "PC5_25") (pintype "bidirectional"))
    )
    (net (code "45") (name "P2_D0") (class "Default")
      (node (ref "CN4") (pin "6") (pinfunction "6_6") (pintype "bidirectional"))
      (node (ref "J10") (pin "4") (pinfunction "R4_4") (pintype "bidirectional"))
      (node (ref "J6") (pin "4") (pinfunction "4_4") (pintype "bidirectional"))
      (node (ref "RN7") (pin "7") (pinfunction "7_7") (pintype "passive"))
    )
    (net (code "46") (name "P2_D0_3V") (class "Default")
      (node (ref "IC4") (pin "5") (pinfunction "1A2_5") (pintype "bidirectional"))
      (node (ref "U1") (pin "39") (pinfunction "PC8_39") (pintype "bidirectional"))
    )
    (net (code "47") (name "P2_D1") (class "Default")
      (node (ref "CN4") (pin "5") (pinfunction "5_5") (pintype "bidirectional"))
      (node (ref "J10") (pin "5") (pinfunction "R5_5") (pintype "bidirectional"))
      (node (ref "J6") (pin "5") (pinfunction "5_5") (pintype "bidirectional"))
      (node (ref "RN7") (pin "8") (pinfunction "8_8") (pintype "passive"))
    )
    (net (code "48") (name "P2_D1_3V") (class "Default")
      (node (ref "IC4") (pin "4") (pinfunction "1A1_4") (pintype "bidirectional"))
      (node (ref "U1") (pin "38") (pinfunction "PC7_38") (pintype "bidirectional"))
    )
    (net (code "49") (name "P2_D2") (class "Default")
      (node (ref "IC4") (pin "11") (pinfunction "2B1_11") (pintype "bidirectional"))
      (node (ref "J10") (pin "3") (pinfunction "R3_3") (pintype "bidirectional"))
      (node (ref "J6") (pin "3") (pinfunction "3_3") (pintype "bidirectional"))
      (node (ref "RN5") (pin "1") (pinfunction "1_1") (pintype "passive"))
      (node (ref "RN7") (pin "3") (pinfunction "3_3") (pintype "passive"))
      (node (ref "RN7") (pin "6") (pinfunction "6_6") (pintype "passive"))
    )
    (net (code "50") (name "P2_D2_3V_IN") (class "Default")
      (node (ref "IC2") (pin "5") (pinfunction "2Y_5") (pintype "bidirectional"))
      (node (ref "U1") (pin "40") (pinfunction "PC9_40") (pintype "bidirectional"))
    )
    (net (code "51") (name "P2_D2_3V_OUT") (class "Default")
      (node (ref "IC4") (pin "6") (pinfunction "2A1_6") (pintype "bidirectional"))
      (node (ref "U1") (pin "29") (pinfunction "PB10_29") (pintype "bidirectional"))
    )
    (net (code "52") (name "P2_D3") (class "Default")
      (node (ref "IC4") (pin "10") (pinfunction "2B2_10") (pintype "bidirectional"))
      (node (ref "J10") (pin "7") (pinfunction "R7_7") (pintype "bidirectional"))
      (node (ref "J6") (pin "7") (pinfunction "7_7") (pintype "bidirectional"))
      (node (ref "RN7") (pin "4") (pinfunction "4_4") (pintype "passive"))
      (node (ref "RN7") (pin "5") (pinfunction "5_5") (pintype "passive"))
    )
    (net (code "53") (name "P2_D3_3V") (class "Default")
      (node (ref "IC4") (pin "7") (pinfunction "2A2_7") (pintype "bidirectional"))
      (node (ref "U1") (pin "27") (pinfunction "PB1_27") (pintype "bidirectional"))
    )
    (net (code "54") (name "P2_LATCH") (class "Default")
      (node (ref "J10") (pin "6") (pinfunction "R6_6") (pintype "bidirectional"))
      (node (ref "J6") (pin "6") (pinfunction "6_6") (pintype "bidirectional"))
      (node (ref "RN5") (pin "3") (pinfunction "3_3") (pintype "passive"))
    )
    (net (code "55") (name "P2_LATCH_3V") (class "Default")
      (node (ref "IC2") (pin "7") (pinfunction "1Y_7") (pintype "bidirectional"))
      (node (ref "U1") (pin "37") (pinfunction "PC6_37") (pintype "bidirectional"))
    )
    (net (code "56") (name "P2_VCC") (class "Default")
      (node (ref "C17") (pin "1") (pinfunction "1_1") (pintype "passive"))
      (node (ref "D2") (pin "A") (pinfunction "A_A") (pintype "passive"))
      (node (ref "IC4") (pin "16") (pinfunction "VCC(B)_16") (pintype "bidirectional"))
      (node (ref "J10") (pin "2") (pinfunction "R2_2") (pintype "bidirectional"))
      (node (ref "J6") (pin "2") (pinfunction "2_2") (pintype "bidirectional"))
      (node (ref "RN2") (pin "5") (pinfunction "5_5") (pintype "passive"))
      (node (ref "RN2") (pin "6") (pinfunction "6_6") (pintype "passive"))
      (node (ref "RN2") (pin "7") (pinfunction "7_7") (pintype "passive"))
      (node (ref "RN2") (pin "8") (pinfunction "8_8") (pintype "passive"))
    )
    (net (code "57") (name "SNES_RESET") (class "Default")
      (node (ref "J4") (pin "1") (pinfunction "1_1") (pintype "bidirectional"))
      (node (ref "U1") (pin "42") (pinfunction "PA9_42") (pintype "bidirectional"))
    )
    (net (code "58") (name "SWCLK") (class "Default")
      (node (ref "J12") (pin "2") (pinfunction "P$2_2") (pintype "passive"))
      (node (ref "J3") (pin "2") (pinfunction "2_2") (pintype "bidirectional"))
      (node (ref "U1") (pin "49") (pinfunction "PA14_49") (pintype "bidirectional"))
    )
    (net (code "59") (name "SWDIO") (class "Default")
      (node (ref "J12") (pin "4") (pinfunction "P$4_4") (pintype "passive"))
      (node (ref "J3") (pin "4") (pinfunction "4_4") (pintype "bidirectional"))
      (node (ref "U1") (pin "46") (pinfunction "PA13_46") (pintype "bidirectional"))
    )
    (net (code "60") (name "SWITCH1") (class "Default")
      (node (ref "S1") (pin "1") (pinfunction "P$1_1") (pintype "bidirectional"))
      (node (ref "S1") (pin "2") (pinfunction "P$1_2") (pintype "bidirectional"))
      (node (ref "U1") (pin "33") (pinfunction "PB12_33") (pintype "bidirectional"))
    )
    (net (code "61") (name "SWITCH2") (class "Default")
      (node (ref "S2") (pin "1") (pinfunction "P$1_1") (pintype "bidirectional"))
      (node (ref "S2") (pin "2") (pinfunction "P$1_2") (pintype "bidirectional"))
      (node (ref "U1") (pin "34") (pinfunction "PB13_34") (pintype "bidirectional"))
    )
    (net (code "62") (name "SWITCH3") (class "Default")
      (node (ref "S3") (pin "1") (pinfunction "P$1_1") (pintype "bidirectional"))
      (node (ref "S3") (pin "2") (pinfunction "P$1_2") (pintype "bidirectional"))
      (node (ref "U1") (pin "41") (pinfunction "PA8_41") (pintype "bidirectional"))
    )
    (net (code "63") (name "SWITCH4") (class "Default")
      (node (ref "S4") (pin "1") (pinfunction "P$1_1") (pintype "bidirectional"))
      (node (ref "S4") (pin "2") (pinfunction "P$1_2") (pintype "bidirectional"))
      (node (ref "U1") (pin "43") (pinfunction "PA10_43") (pintype "bidirectional"))
    )
    (net (code "64") (name "USBHS_DM") (class "Default")
      (node (ref "J2") (pin "2") (pinfunction "2_2") (pintype "bidirectional"))
      (node (ref "U1") (pin "35") (pinfunction "PB14_35") (pintype "bidirectional"))
    )
    (net (code "65") (name "USBHS_DP") (class "Default")
      (node (ref "J2") (pin "3") (pinfunction "3_3") (pintype "bidirectional"))
      (node (ref "U1") (pin "36") (pinfunction "PB15_36") (pintype "bidirectional"))
    )
    (net (code "66") (name "V+") (class "Default")
      (node (ref "C10") (pin "2") (pinfunction "2_2") (pintype "passive"))
      (node (ref "C11") (pin "2") (pinfunction "2_2") (pintype "passive"))
      (node (ref "C12") (pin "2") (pinfunction "2_2") (pintype "passive"))
      (node (ref "C13") (pin "1") (pinfunction "1_1") (pintype "passive"))
      (node (ref "C14") (pin "2") (pinfunction "2_2") (pintype "passive"))
      (node (ref "C16") (pin "2") (pinfunction "2_2") (pintype "passive"))
      (node (ref "C4") (pin "2") (pinfunction "2_2") (pintype "passive"))
      (node (ref "C5") (pin "1") (pinfunction "1_1") (pintype "passive"))
      (node (ref "C7") (pin "2") (pinfunction "2_2") (pintype "passive"))
      (node (ref "C8") (pin "2") (pinfunction "2_2") (pintype "passive"))
      (node (ref "C9") (pin "2") (pinfunction "2_2") (pintype "passive"))
      (node (ref "IC1") (pin "8") (pinfunction "VCC_8") (pintype "bidirectional"))
      (node (ref "IC2") (pin "8") (pinfunction "VCC_8") (pintype "bidirectional"))
      (node (ref "IC3") (pin "1") (pinfunction "VCC(A)_1") (pintype "bidirectional"))
      (node (ref "IC4") (pin "1") (pinfunction "VCC(A)_1") (pintype "bidirectional"))
      (node (ref "J11") (pin "10") (pinfunction "L2_10") (pintype "bidirectional"))
      (node (ref "J11") (pin "2") (pinfunction "R2_2") (pintype "bidirectional"))
      (node (ref "J12") (pin "1") (pinfunction "P$1_1") (pintype "passive"))
      (node (ref "J13") (pin "1") (pinfunction "1_1") (pintype "bidirectional"))
      (node (ref "J3") (pin "1") (pinfunction "1_1") (pintype "bidirectional"))
      (node (ref "J5") (pin "1") (pinfunction "4_1") (pintype "bidirectional"))
      (node (ref "J7") (pin "10") (pinfunction "10_10") (pintype "bidirectional"))
      (node (ref "J7") (pin "2") (pinfunction "2_2") (pintype "bidirectional"))
      (node (ref "R1") (pin "2") (pinfunction "2_2") (pintype "passive"))
      (node (ref "R3") (pin "2") (pinfunction "2_2") (pintype "passive"))
      (node (ref "U1") (pin "1") (pinfunction "VBAT_1") (pintype "power_in"))
      (node (ref "U1") (pin "13") (pinfunction "VDDA/VREF+_13") (pintype "power_in"))
      (node (ref "U1") (pin "19") (pinfunction "VDD_19") (pintype "power_in"))
      (node (ref "U1") (pin "32") (pinfunction "VDD_32") (pintype "power_in"))
      (node (ref "U1") (pin "48") (pinfunction "VDD_48") (pintype "power_in"))
      (node (ref "U1") (pin "64") (pinfunction "VDD_64") (pintype "power_in"))
      (node (ref "U2") (pin "2") (pinfunction "OUT_2") (pintype "passive"))
      (node (ref "U2") (pin "4") (pinfunction "OUT_4") (pintype "passive"))
    )
    (net (code "67") (name "V1_CLOCK") (class "Default")
      (node (ref "J11") (pin "8") (pinfunction "R8_8") (pintype "bidirectional"))
      (node (ref "J7") (pin "8") (pinfunction "8_8") (pintype "bidirectional"))
      (node (ref "U1") (pin "56") (pinfunction "PB4(NJTRST)_56") (pintype "bidirectional"))
    )
    (net (code "68") (name "V1_D0") (class "Default")
      (node (ref "J11") (pin "4") (pinfunction "R4_4") (pintype "bidirectional"))
      (node (ref "J7") (pin "4") (pinfunction "4_4") (pintype "bidirectional"))
      (node (ref "U1") (pin "59") (pinfunction "PB7_59") (pintype "bidirectional"))
    )
    (net (code "69") (name "V1_D1") (class "Default")
      (node (ref "J11") (pin "5") (pinfunction "R5_5") (pintype "bidirectional"))
      (node (ref "J7") (pin "5") (pinfunction "5_5") (pintype "bidirectional"))
      (node (ref "U1") (pin "58") (pinfunction "PB6_58") (pintype "bidirectional"))
    )
    (net (code "70") (name "V1_D2") (class "Default")
      (node (ref "J11") (pin "3") (pinfunction "R3_3") (pintype "bidirectional"))
      (node (ref "J7") (pin "3") (pinfunction "3_3") (pintype "bidirectional"))
    )
    (net (code "71") (name "V1_D3") (class "Default")
      (node (ref "J11") (pin "7") (pinfunction "R7_7") (pintype "bidirectional"))
      (node (ref "J7") (pin "7") (pinfunction "7_7") (pintype "bidirectional"))
    )
    (net (code "72") (name "V1_LATCH") (class "Default")
      (node (ref "J11") (pin "6") (pinfunction "R6_6") (pintype "bidirectional"))
      (node (ref "J7") (pin "6") (pinfunction "6_6") (pintype "bidirectional"))
      (node (ref "U1") (pin "57") (pinfunction "PB5_57") (pintype "bidirectional"))
    )
    (net (code "73") (name "V2_CLOCK") (class "Default")
      (node (ref "J11") (pin "16") (pinfunction "L8_16") (pintype "bidirectional"))
      (node (ref "J7") (pin "16") (pinfunction "16_16") (pintype "bidirectional"))
      (node (ref "U1") (pin "50") (pinfunction "PA15_50") (pintype "bidirectional"))
    )
    (net (code "74") (name "V2_D0") (class "Default")
      (node (ref "J11") (pin "12") (pinfunction "L4_12") (pintype "bidirectional"))
      (node (ref "J7") (pin "12") (pinfunction "12_12") (pintype "bidirectional"))
      (node (ref "U1") (pin "53") (pinfunction "PC12_53") (pintype "bidirectional"))
    )
    (net (code "75") (name "V2_D1") (class "Default")
      (node (ref "J11") (pin "13") (pinfunction "L5_13") (pintype "bidirectional"))
      (node (ref "J7") (pin "13") (pinfunction "13_13") (pintype "bidirectional"))
      (node (ref "U1") (pin "52") (pinfunction "PC11_52") (pintype "bidirectional"))
    )
    (net (code "76") (name "V2_D2") (class "Default")
      (node (ref "J11") (pin "11") (pinfunction "L3_11") (pintype "bidirectional"))
      (node (ref "J7") (pin "11") (pinfunction "11_11") (pintype "bidirectional"))
      (node (ref "U1") (pin "55") (pinfunction "PB3(JTDO/TRACESWO)_55") (pintype "bidirectional"))
    )
    (net (code "77") (name "V2_D3") (class "Default")
      (node (ref "J11") (pin "15") (pinfunction "L7_15") (pintype "bidirectional"))
      (node (ref "J7") (pin "15") (pinfunction "15_15") (pintype "bidirectional"))
      (node (ref "U1") (pin "54") (pinfunction "PD2_54") (pintype "bidirectional"))
    )
    (net (code "78") (name "V2_LATCH") (class "Default")
      (node (ref "J11") (pin "14") (pinfunction "L6_14") (pintype "bidirectional"))
      (node (ref "J7") (pin "14") (pinfunction "14_14") (pintype "bidirectional"))
      (node (ref "U1") (pin "51") (pinfunction "PC10_51") (pintype "bidirectional"))
    )
    (net (code "79") (name "unconnected-(CN1-Pad8)") (class "Default")
      (node (ref "CN1") (pin "8") (pinfunction "8_8") (pintype "bidirectional"))
    )
    (net (code "80") (name "unconnected-(CN2-Pad7)") (class "Default")
      (node (ref "CN2") (pin "7") (pinfunction "7_7") (pintype "bidirectional"))
    )
    (net (code "81") (name "unconnected-(CN3-Pad5)") (class "Default")
      (node (ref "CN3") (pin "5") (pinfunction "5_5") (pintype "bidirectional"))
    )
    (net (code "82") (name "unconnected-(CN3-Pad6)") (class "Default")
      (node (ref "CN3") (pin "6") (pinfunction "6_6") (pintype "bidirectional"))
    )
    (net (code "83") (name "unconnected-(CN4-Pad7)") (class "Default")
      (node (ref "CN4") (pin "7") (pinfunction "7_7") (pintype "bidirectional"))
    )
    (net (code "84") (name "unconnected-(CN4-Pad8)") (class "Default")
      (node (ref "CN4") (pin "8") (pinfunction "8_8") (pintype "bidirectional"))
    )
    (net (code "85") (name "unconnected-(J1-Pad4)") (class "Default")
      (node (ref "J1") (pin "4") (pinfunction "4_4") (pintype "passive"))
    )
    (net (code "86") (name "unconnected-(J12-P$6-Pad6)") (class "Default")
      (node (ref "J12") (pin "6") (pinfunction "P$6_6") (pintype "passive"))
    )
    (net (code "87") (name "unconnected-(J12-P$7-Pad7)") (class "Default")
      (node (ref "J12") (pin "7") (pinfunction "P$7_7") (pintype "passive"))
    )
    (net (code "88") (name "unconnected-(J12-P$8-Pad8)") (class "Default")
      (node (ref "J12") (pin "8") (pinfunction "P$8_8") (pintype "passive"))
    )
    (net (code "89") (name "unconnected-(RN1-Pad4)") (class "Default")
      (node (ref "RN1") (pin "4") (pinfunction "4_4") (pintype "passive"))
    )
    (net (code "90") (name "unconnected-(RN2-Pad3)") (class "Default")
      (node (ref "RN2") (pin "3") (pinfunction "3_3") (pintype "passive"))
    )
    (net (code "91") (name "unconnected-(RN4-Pad1)") (class "Default")
      (node (ref "RN4") (pin "1") (pinfunction "1_1") (pintype "passive"))
    )
    (net (code "92") (name "unconnected-(RN4-Pad8)") (class "Default")
      (node (ref "RN4") (pin "8") (pinfunction "8_8") (pintype "passive"))
    )
    (net (code "93") (name "unconnected-(RN5-Pad2)") (class "Default")
      (node (ref "RN5") (pin "2") (pinfunction "2_2") (pintype "passive"))
    )
    (net (code "94") (name "unconnected-(RN5-Pad7)") (class "Default")
      (node (ref "RN5") (pin "7") (pinfunction "7_7") (pintype "passive"))
    )
    (net (code "95") (name "unconnected-(U1-PA3-Pad17)") (class "Default")
      (node (ref "U1") (pin "17") (pinfunction "PA3_17") (pintype "bidirectional"))
    )
    (net (code "96") (name "unconnected-(U1-PC13{slash}EVENTOUT-Pad2)") (class "Default")
      (node (ref "U1") (pin "2") (pinfunction "PC13/EVENTOUT_2") (pintype "bidirectional"))
    )
    (net (code "97") (name "unconnected-(U1-PC14-OSC32_IN(PC14){slash}EVENTOUT-Pad3)") (class "Default")
      (node (ref "U1") (pin "3") (pinfunction "PC14-OSC32_IN(PC14)/EVENTOUT_3") (pintype "bidirectional"))
    )
    (net (code "98") (name "unconnected-(U1-PC15-OSC32_OUT(PC15){slash}EVENTOUT-Pad4)") (class "Default")
      (node (ref "U1") (pin "4") (pinfunction "PC15-OSC32_OUT(PC15)/EVENTOUT_4") (pintype "bidirectional"))
    )
  )
)
